# Peripheral-ICs.net
KiCad netlist of a schematic drawn in Altium Designer
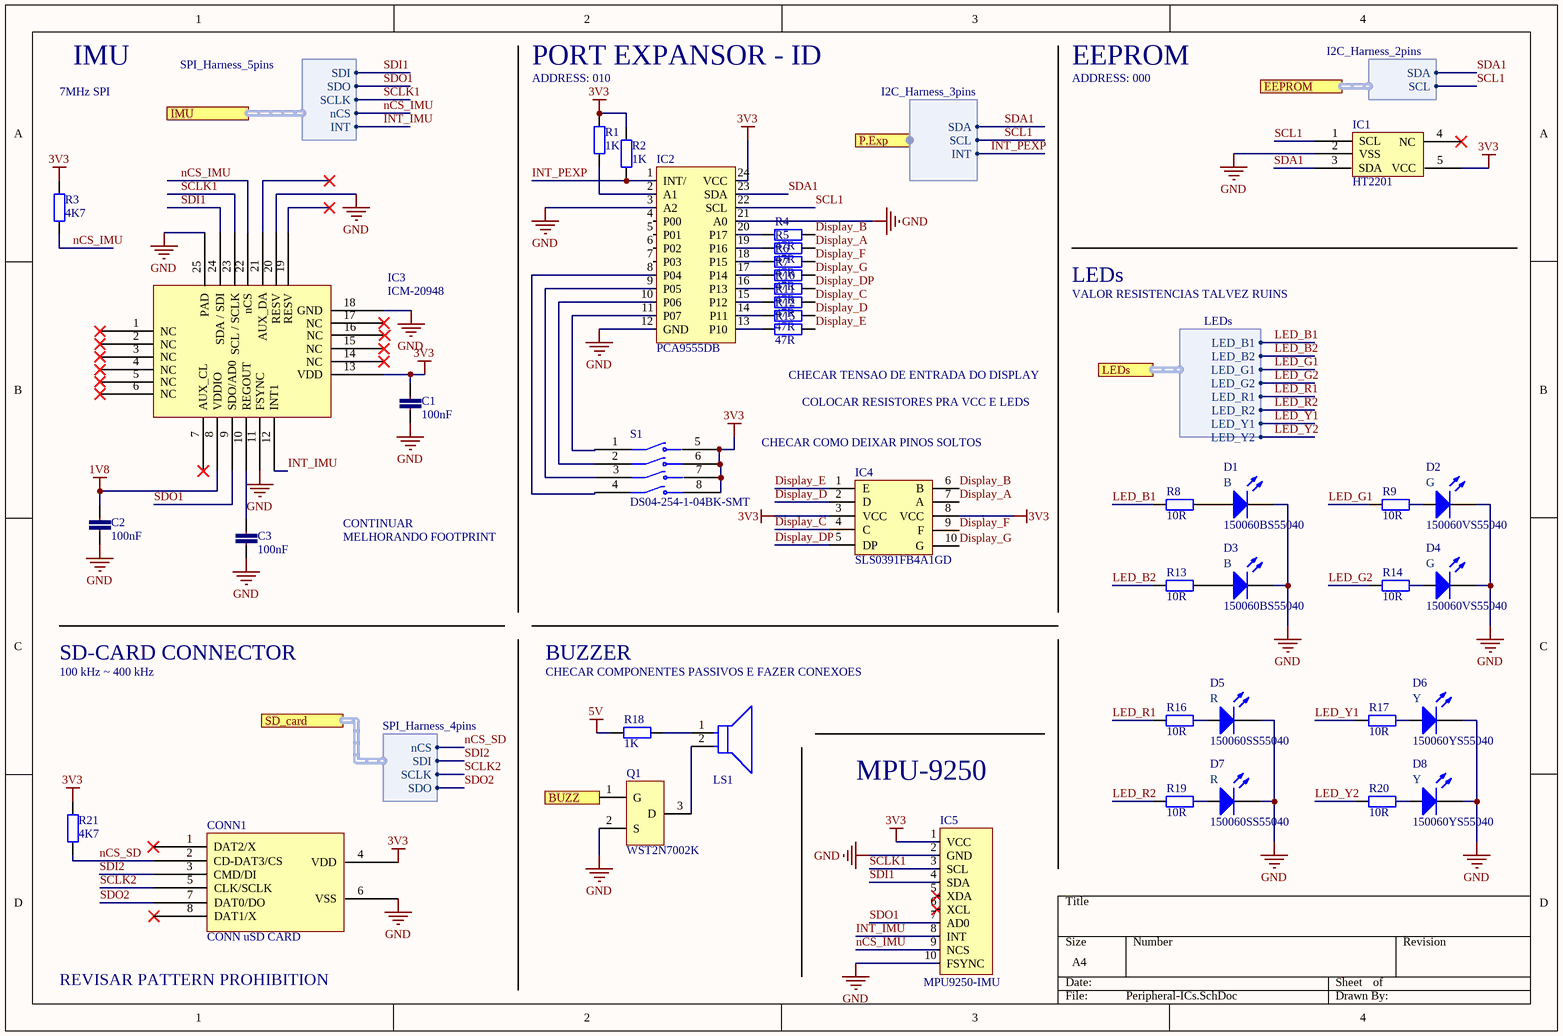
[diagram p0: Peripheral-ICs.SchDoc]

(export (version "E")
  (design (tool "Eeschema 10.0.6"))
  (components
    (comp (ref "C1")
      (value "100nF")
      (footprint "CAP CER 0603")
      (description "Multilayer Ceramic Capacitors MLCC - SMD/SMT 25V 0.1uF 0603 Y5V -20/+80%")
      (fields (field (name "MFR") "KEMET"))
      (libsource (lib "SSL-2020-SchLib1") (part "CAP CER 0603 25V 100nF"))
    )
    (comp (ref "C2")
      (value "100nF")
      (footprint "CAP CER 0603")
      (description "Multilayer Ceramic Capacitors MLCC - SMD/SMT 25V 0.1uF 0603 Y5V -20/+80%")
      (fields (field (name "MFR") "KEMET"))
      (libsource (lib "SSL-2020-SchLib1") (part "CAP CER 0603 25V 100nF"))
    )
    (comp (ref "C3")
      (value "100nF")
      (footprint "CAP CER 0603")
      (description "Multilayer Ceramic Capacitors MLCC - SMD/SMT 25V 0.1uF 0603 Y5V -20/+80%")
      (fields (field (name "MFR") "KEMET"))
      (libsource (lib "SSL-2020-SchLib1") (part "CAP CER 0603 25V 100nF"))
    )
    (comp (ref "CONN1")
      (value "CONN uSD CARD")
      (footprint "2908-05WB-MG")
      (description "8 Position Card Connector Secure Digital - microSD™ Surface Mount, Right Angle Gold")
      (libsource (lib "SSL-2020-SchLib1") (part "2908-05WB-MG"))
    )
    (comp (ref "D1")
      (value "150060BS55040")
      (footprint "LED 0603 BLUE")
      (description "Standard LEDs - SMD WL-SMCD SMD Mono SMD 0603 Blue 465nm")
      (fields (field (name "MFR") "Wurth Elektronik"))
      (libsource (lib "SSL-2020-SchLib1") (part "150060BS55040"))
    )
    (comp (ref "D2")
      (value "150060VS55040")
      (footprint "LED 0603 GREEN")
      (description "Standard LEDs - SMD WL-SMCD SMD MonoChip 0603 BrtGrn 575nm")
      (fields (field (name "MFR") "Wurth Elektronik"))
      (libsource (lib "SSL-2020-SchLib1") (part "150060VS55040"))
    )
    (comp (ref "D3")
      (value "150060BS55040")
      (footprint "LED 0603 BLUE")
      (description "Standard LEDs - SMD WL-SMCD SMD Mono SMD 0603 Blue 465nm")
      (fields (field (name "MFR") "Wurth Elektronik"))
      (libsource (lib "SSL-2020-SchLib1") (part "150060BS55040"))
    )
    (comp (ref "D4")
      (value "150060VS55040")
      (footprint "LED 0603 GREEN")
      (description "Standard LEDs - SMD WL-SMCD SMD MonoChip 0603 BrtGrn 575nm")
      (fields (field (name "MFR") "Wurth Elektronik"))
      (libsource (lib "SSL-2020-SchLib1") (part "150060VS55040"))
    )
    (comp (ref "D5")
      (value "150060SS55040")
      (footprint "LED 0603 RED")
      (description "Standard LEDs - SMD WL-SMCD SMD MonoChip 0603 Super Red 645nm")
      (fields (field (name "MFR") "Wurth Elektronik"))
      (libsource (lib "SSL-2020-SchLib1") (part "150060SS55040"))
    )
    (comp (ref "D6")
      (value "150060YS55040")
      (footprint "LED 0603 YELLOW")
      (description "Standard LEDs - SMD WL-SMCD SMD MonoChip 0603 Yllw 591nm")
      (fields (field (name "MFR") "Wurth Elektronik"))
      (libsource (lib "SSL-2020-SchLib1") (part "150060YS55040"))
    )
    (comp (ref "D7")
      (value "150060SS55040")
      (footprint "LED 0603 RED")
      (description "Standard LEDs - SMD WL-SMCD SMD MonoChip 0603 Super Red 645nm")
      (fields (field (name "MFR") "Wurth Elektronik"))
      (libsource (lib "SSL-2020-SchLib1") (part "150060SS55040"))
    )
    (comp (ref "D8")
      (value "150060YS55040")
      (footprint "LED 0603 YELLOW")
      (description "Standard LEDs - SMD WL-SMCD SMD MonoChip 0603 Yllw 591nm")
      (fields (field (name "MFR") "Wurth Elektronik"))
      (libsource (lib "SSL-2020-SchLib1") (part "150060YS55040"))
    )
    (comp (ref "IC1")
      (value "HT2201")
      (footprint "SOT-23-5")
      (description "EEPROM EEPROM 1KB (128 X 8) I2C SOT-23-5 ROHS")
      (fields (field (name "MFR") "Holtek Semicon"))
      (libsource (lib "SSL-2020-SchLib1") (part "HT2201"))
    )
    (comp (ref "IC2")
      (value "PCA9555DB")
      (footprint "SSOP-24")
      (description "INTERFACE - I/O EXPANDERS SSOP-24 ROHS")
      (fields (field (name "MFR") "NXP Semicon"))
      (libsource (lib "SSL-2020-SchLib1") (part "PCA9555DB"))
    )
    (comp (ref "IC3")
      (value "ICM-20948")
      (footprint "ICM-20948")
      (description "IMU ACCEL/GYRO/COMPI2C/SPI 24QFN")
      (libsource (lib "SSL-2020-SchLib1") (part "ICM-20948"))
    )
    (comp (ref "IC4")
      (value "SLS0391FB4A1GD")
      (footprint "LDS-SMHTA304RISITR")
      (description "1 0.39''(9.91MM) ANODE(POSITIVE ELECTRODE) BLUE 473NM SMD LED SEGMENT DISPLAY ROHS")
      (fields (field (name "MFR") "SUNLIGHT"))
      (libsource (lib "SSL-2020-SchLib1") (part "SLS0391FB4A1GD"))
    )
    (comp (ref "IC5")
      (value "MPU9250-IMU")
      (footprint "MPU9250-IMU")
      (libsource (lib "SSL-2020-SchLib1") (part "MPU9250-IMU"))
    )
    (comp (ref "LS1")
      (value "Speak_TDK_PS1420P02CT_eec")
      (footprint "TDK_PS1420P02CT_0")
      (description "SPEAK AUDIO PIEZO TRANSDUCER 30V TH")
      (fields (field (name "PART NUMBER") "PS1420P02CT") (field (name "MANUFACTURER") "TDK"))
      (libsource (lib "SSL-2020-SchLib1") (part "Speak_TDK_PS1420P02CT_eec"))
    )
    (comp (ref "Q1")
      (value "WST2N7002K")
      (footprint "SOT-23-3")
      (description "MOSFET N TRENCH 60V 300MA 2.5V @ 250UA 3 ? @ 500MA,10V SOT-23(SOT-23-3) ROHS")
      (fields (field (name "MFR") "Winsok Semicon"))
      (libsource (lib "SSL-2020-SchLib1") (part "WST2N7002K"))
    )
    (comp (ref "R1")
      (value "1K")
      (footprint "RES SMD 0603")
      (description "Thick Film Resistors 1/10Watt 1Kohms 1% Commercial Use")
      (fields (field (name "MFR") "Vishay / Dale"))
      (libsource (lib "SSL-2020-SchLib1") (part "RES SMD 0603 1K"))
    )
    (comp (ref "R2")
      (value "1K")
      (footprint "RES SMD 0603")
      (description "Thick Film Resistors 1/10Watt 1Kohms 1% Commercial Use")
      (fields (field (name "MFR") "Vishay / Dale"))
      (libsource (lib "SSL-2020-SchLib1") (part "RES SMD 0603 1K"))
    )
    (comp (ref "R3")
      (value "4K7")
      (footprint "RES SMD 0603")
      (libsource (lib "SSL-2020-SchLib1") (part "RES SMD 0603 4K7"))
    )
    (comp (ref "R4")
      (value "47R")
      (footprint "RES SMD 0603")
      (description "Thick Film Resistors 1/10Watt 47ohms 1% Commercial Use")
      (fields (field (name "MFR") "Vishay / Dale"))
      (libsource (lib "SSL-2020-SchLib1") (part "RES SMD 0603 47R"))
    )
    (comp (ref "R5")
      (value "47R")
      (footprint "RES SMD 0603")
      (description "Thick Film Resistors 1/10Watt 47ohms 1% Commercial Use")
      (fields (field (name "MFR") "Vishay / Dale"))
      (libsource (lib "SSL-2020-SchLib1") (part "RES SMD 0603 47R"))
    )
    (comp (ref "R6")
      (value "47R")
      (footprint "RES SMD 0603")
      (description "Thick Film Resistors 1/10Watt 47ohms 1% Commercial Use")
      (fields (field (name "MFR") "Vishay / Dale"))
      (libsource (lib "SSL-2020-SchLib1") (part "RES SMD 0603 47R"))
    )
    (comp (ref "R7")
      (value "47R")
      (footprint "RES SMD 0603")
      (description "Thick Film Resistors 1/10Watt 47ohms 1% Commercial Use")
      (fields (field (name "MFR") "Vishay / Dale"))
      (libsource (lib "SSL-2020-SchLib1") (part "RES SMD 0603 47R"))
    )
    (comp (ref "R8")
      (value "10R")
      (footprint "RES SMD 0603")
      (description "Thick Film Resistors 1/10Watt 10ohms 1% Commercial Use")
      (fields (field (name "MFR") "Vishay / Dale"))
      (libsource (lib "SSL-2020-SchLib1") (part "RES SMD 0603 10R"))
    )
    (comp (ref "R9")
      (value "10R")
      (footprint "RES SMD 0603")
      (description "Thick Film Resistors 1/10Watt 10ohms 1% Commercial Use")
      (fields (field (name "MFR") "Vishay / Dale"))
      (libsource (lib "SSL-2020-SchLib1") (part "RES SMD 0603 10R"))
    )
    (comp (ref "R10")
      (value "47R")
      (footprint "RES SMD 0603")
      (description "Thick Film Resistors 1/10Watt 47ohms 1% Commercial Use")
      (fields (field (name "MFR") "Vishay / Dale"))
      (libsource (lib "SSL-2020-SchLib1") (part "RES SMD 0603 47R"))
    )
    (comp (ref "R11")
      (value "47R")
      (footprint "RES SMD 0603")
      (description "Thick Film Resistors 1/10Watt 47ohms 1% Commercial Use")
      (fields (field (name "MFR") "Vishay / Dale"))
      (libsource (lib "SSL-2020-SchLib1") (part "RES SMD 0603 47R"))
    )
    (comp (ref "R12")
      (value "47R")
      (footprint "RES SMD 0603")
      (description "Thick Film Resistors 1/10Watt 47ohms 1% Commercial Use")
      (fields (field (name "MFR") "Vishay / Dale"))
      (libsource (lib "SSL-2020-SchLib1") (part "RES SMD 0603 47R"))
    )
    (comp (ref "R13")
      (value "10R")
      (footprint "RES SMD 0603")
      (description "Thick Film Resistors 1/10Watt 10ohms 1% Commercial Use")
      (fields (field (name "MFR") "Vishay / Dale"))
      (libsource (lib "SSL-2020-SchLib1") (part "RES SMD 0603 10R"))
    )
    (comp (ref "R14")
      (value "10R")
      (footprint "RES SMD 0603")
      (description "Thick Film Resistors 1/10Watt 10ohms 1% Commercial Use")
      (fields (field (name "MFR") "Vishay / Dale"))
      (libsource (lib "SSL-2020-SchLib1") (part "RES SMD 0603 10R"))
    )
    (comp (ref "R15")
      (value "47R")
      (footprint "RES SMD 0603")
      (description "Thick Film Resistors 1/10Watt 47ohms 1% Commercial Use")
      (fields (field (name "MFR") "Vishay / Dale"))
      (libsource (lib "SSL-2020-SchLib1") (part "RES SMD 0603 47R"))
    )
    (comp (ref "R16")
      (value "10R")
      (footprint "RES SMD 0603")
      (description "Thick Film Resistors 1/10Watt 10ohms 1% Commercial Use")
      (fields (field (name "MFR") "Vishay / Dale"))
      (libsource (lib "SSL-2020-SchLib1") (part "RES SMD 0603 10R"))
    )
    (comp (ref "R17")
      (value "10R")
      (footprint "RES SMD 0603")
      (description "Thick Film Resistors 1/10Watt 10ohms 1% Commercial Use")
      (fields (field (name "MFR") "Vishay / Dale"))
      (libsource (lib "SSL-2020-SchLib1") (part "RES SMD 0603 10R"))
    )
    (comp (ref "R18")
      (value "1K")
      (footprint "RES SMD 0603")
      (description "Thick Film Resistors 1/10Watt 1Kohms 1% Commercial Use")
      (fields (field (name "MFR") "Vishay / Dale"))
      (libsource (lib "") (part "RES SMD 0603 1K_1"))
    )
    (comp (ref "R19")
      (value "10R")
      (footprint "RES SMD 0603")
      (description "Thick Film Resistors 1/10Watt 10ohms 1% Commercial Use")
      (fields (field (name "MFR") "Vishay / Dale"))
      (libsource (lib "SSL-2020-SchLib1") (part "RES SMD 0603 10R"))
    )
    (comp (ref "R20")
      (value "10R")
      (footprint "RES SMD 0603")
      (description "Thick Film Resistors 1/10Watt 10ohms 1% Commercial Use")
      (fields (field (name "MFR") "Vishay / Dale"))
      (libsource (lib "SSL-2020-SchLib1") (part "RES SMD 0603 10R"))
    )
    (comp (ref "R21")
      (value "4K7")
      (footprint "RES SMD 0603")
      (libsource (lib "SSL-2020-SchLib1") (part "RES SMD 0603 4K7"))
    )
    (comp (ref "S1")
      (value "DS04-254-1-04BK-SMT")
      (footprint "DS04-254-1-04BK-SMT")
      (description "Dip Switch SPST 4 Position Surface Mount Slide (Standard) Actuator 25mA 24VDC")
      (libsource (lib "SSL-2020-SchLib1") (part "DS04-254-1-04BK-SMT"))
    )
  )
  (nets
    (net (code "7") (name "/BUZZ") (class "Default")
      (node (ref "Q1") (pin "1") (pinfunction "G_1") (pintype "passive"))
    )
    (net (code "8") (name "/Display_A") (class "Default")
      (node (ref "IC4") (pin "7") (pinfunction "A_7") (pintype "passive"))
      (node (ref "R5") (pin "2") (pinfunction "2_2") (pintype "passive"))
    )
    (net (code "9") (name "/Display_B") (class "Default")
      (node (ref "IC4") (pin "6") (pinfunction "B_6") (pintype "passive"))
      (node (ref "R4") (pin "2") (pinfunction "2_2") (pintype "passive"))
    )
    (net (code "10") (name "/Display_C") (class "Default")
      (node (ref "IC4") (pin "4") (pinfunction "C_4") (pintype "passive"))
      (node (ref "R11") (pin "2") (pinfunction "2_2") (pintype "passive"))
    )
    (net (code "11") (name "/Display_D") (class "Default")
      (node (ref "IC4") (pin "2") (pinfunction "D_2") (pintype "passive"))
      (node (ref "R12") (pin "2") (pinfunction "2_2") (pintype "passive"))
    )
    (net (code "12") (name "/Display_DP") (class "Default")
      (node (ref "IC4") (pin "5") (pinfunction "DP_5") (pintype "passive"))
      (node (ref "R10") (pin "2") (pinfunction "2_2") (pintype "passive"))
    )
    (net (code "13") (name "/Display_E") (class "Default")
      (node (ref "IC4") (pin "1") (pinfunction "E_1") (pintype "passive"))
      (node (ref "R15") (pin "2") (pinfunction "2_2") (pintype "passive"))
    )
    (net (code "14") (name "/Display_F") (class "Default")
      (node (ref "IC4") (pin "9") (pinfunction "F_9") (pintype "passive"))
      (node (ref "R6") (pin "2") (pinfunction "2_2") (pintype "passive"))
    )
    (net (code "15") (name "/Display_G") (class "Default")
      (node (ref "IC4") (pin "10") (pinfunction "G_10") (pintype "passive"))
      (node (ref "R7") (pin "2") (pinfunction "2_2") (pintype "passive"))
    )
    (net (code "16") (name "/INT_IMU") (class "Default")
      (node (ref "IC3") (pin "12") (pinfunction "INT1_12") (pintype "passive"))
      (node (ref "IC5") (pin "8") (pinfunction "INT_8") (pintype "passive"))
    )
    (net (code "17") (name "/INT_PEXP") (class "Default")
      (node (ref "IC2") (pin "1") (pinfunction "INT/_1") (pintype "passive"))
      (node (ref "R2") (pin "1") (pinfunction "1_1") (pintype "passive"))
    )
    (net (code "18") (name "/LED_B1") (class "Default")
      (node (ref "R8") (pin "2") (pinfunction "2_2") (pintype "passive"))
    )
    (net (code "19") (name "/LED_B2") (class "Default")
      (node (ref "R13") (pin "2") (pinfunction "2_2") (pintype "passive"))
    )
    (net (code "20") (name "/LED_G1") (class "Default")
      (node (ref "R9") (pin "2") (pinfunction "2_2") (pintype "passive"))
    )
    (net (code "21") (name "/LED_G2") (class "Default")
      (node (ref "R14") (pin "2") (pinfunction "2_2") (pintype "passive"))
    )
    (net (code "22") (name "/LED_R1") (class "Default")
      (node (ref "R16") (pin "2") (pinfunction "2_2") (pintype "passive"))
    )
    (net (code "23") (name "/LED_R2") (class "Default")
      (node (ref "R19") (pin "2") (pinfunction "2_2") (pintype "passive"))
    )
    (net (code "24") (name "/LED_Y1") (class "Default")
      (node (ref "R17") (pin "2") (pinfunction "2_2") (pintype "passive"))
    )
    (net (code "25") (name "/LED_Y2") (class "Default")
      (node (ref "R20") (pin "2") (pinfunction "2_2") (pintype "passive"))
    )
    (net (code "26") (name "/SCL1") (class "Default")
      (node (ref "IC1") (pin "1") (pinfunction "SCL_1") (pintype "passive"))
      (node (ref "IC2") (pin "22") (pinfunction "SCL_22") (pintype "passive"))
    )
    (net (code "27") (name "/SCLK1") (class "Default")
      (node (ref "IC3") (pin "23") (pinfunction "SCL_/_SCLK_23") (pintype "passive"))
      (node (ref "IC5") (pin "3") (pinfunction "SCL_3") (pintype "passive"))
    )
    (net (code "28") (name "/SCLK2") (class "Default")
      (node (ref "CONN1") (pin "5") (pinfunction "CLK/SCLK_5") (pintype "passive"))
    )
    (net (code "29") (name "/SDA1") (class "Default")
      (node (ref "IC1") (pin "3") (pinfunction "SDA_3") (pintype "passive"))
      (node (ref "IC2") (pin "23") (pinfunction "SDA_23") (pintype "passive"))
    )
    (net (code "30") (name "/SDI1") (class "Default")
      (node (ref "IC3") (pin "24") (pinfunction "SDA_/_SDI_24") (pintype "passive"))
      (node (ref "IC5") (pin "4") (pinfunction "SDA_4") (pintype "passive"))
    )
    (net (code "31") (name "/SDI2") (class "Default")
      (node (ref "CONN1") (pin "3") (pinfunction "CMD/DI_3") (pintype "passive"))
    )
    (net (code "32") (name "/SDO1") (class "Default")
      (node (ref "IC3") (pin "9") (pinfunction "SDO/AD0_9") (pintype "passive"))
      (node (ref "IC5") (pin "7") (pinfunction "AD0_7") (pintype "passive"))
    )
    (net (code "33") (name "/SDO2") (class "Default")
      (node (ref "CONN1") (pin "7") (pinfunction "DAT0/DO_7") (pintype "power_in"))
    )
    (net (code "34") (name "/nCS_IMU") (class "Default")
      (node (ref "IC3") (pin "22") (pinfunction "nCS_22") (pintype "passive"))
      (node (ref "IC5") (pin "9") (pinfunction "NCS_9") (pintype "passive"))
      (node (ref "R3") (pin "1") (pinfunction "1_1") (pintype "passive"))
    )
    (net (code "35") (name "/nCS_SD") (class "Default")
      (node (ref "CONN1") (pin "2") (pinfunction "CD-DAT3/CS_2") (pintype "passive"))
      (node (ref "R21") (pin "1") (pinfunction "1_1") (pintype "passive"))
    )
    (net (code "41") (name "1V8") (class "Default")
      (node (ref "C2") (pin "1") (pinfunction "1_1") (pintype "passive"))
      (node (ref "IC3") (pin "8") (pinfunction "VDDIO_8") (pintype "passive"))
    )
    (net (code "42") (name "3V3") (class "Default")
      (node (ref "C1") (pin "1") (pinfunction "1_1") (pintype "passive"))
      (node (ref "CONN1") (pin "4") (pinfunction "VDD_4") (pintype "passive"))
      (node (ref "IC1") (pin "5") (pinfunction "VCC_5") (pintype "passive"))
      (node (ref "IC2") (pin "24") (pinfunction "VCC_24") (pintype "passive"))
      (node (ref "IC3") (pin "13") (pinfunction "VDD_13") (pintype "passive"))
      (node (ref "IC4") (pin "3") (pinfunction "VCC_3") (pintype "passive"))
      (node (ref "IC4") (pin "8") (pinfunction "VCC_8") (pintype "passive"))
      (node (ref "IC5") (pin "1") (pinfunction "VCC_1") (pintype "passive"))
      (node (ref "R1") (pin "2") (pinfunction "2_2") (pintype "passive"))
      (node (ref "R2") (pin "2") (pinfunction "2_2") (pintype "passive"))
      (node (ref "R21") (pin "2") (pinfunction "2_2") (pintype "passive"))
      (node (ref "R3") (pin "2") (pinfunction "2_2") (pintype "passive"))
      (node (ref "S1") (pin "5") (pinfunction "5_5") (pintype "passive"))
      (node (ref "S1") (pin "6") (pinfunction "6_6") (pintype "passive"))
      (node (ref "S1") (pin "7") (pinfunction "7_7") (pintype "passive"))
      (node (ref "S1") (pin "8") (pinfunction "8_8") (pintype "passive"))
    )
    (net (code "43") (name "5V") (class "Default")
      (node (ref "R18") (pin "2") (pinfunction "2_2") (pintype "passive"))
    )
    (net (code "44") (name "GND") (class "Default")
      (node (ref "C1") (pin "2") (pinfunction "2_2") (pintype "passive"))
      (node (ref "C2") (pin "2") (pinfunction "2_2") (pintype "passive"))
      (node (ref "C3") (pin "2") (pinfunction "2_2") (pintype "passive"))
      (node (ref "CONN1") (pin "6") (pinfunction "VSS_6") (pintype "passive"))
      (node (ref "D1") (pin "2") (pinfunction "N_2") (pintype "passive"))
      (node (ref "D2") (pin "2") (pinfunction "N_2") (pintype "passive"))
      (node (ref "D3") (pin "2") (pinfunction "N_2") (pintype "passive"))
      (node (ref "D4") (pin "2") (pinfunction "N_2") (pintype "passive"))
      (node (ref "D5") (pin "2") (pinfunction "N_2") (pintype "passive"))
      (node (ref "D6") (pin "2") (pinfunction "N_2") (pintype "passive"))
      (node (ref "D7") (pin "2") (pinfunction "N_2") (pintype "passive"))
      (node (ref "D8") (pin "2") (pinfunction "N_2") (pintype "passive"))
      (node (ref "IC1") (pin "2") (pinfunction "VSS_2") (pintype "passive"))
      (node (ref "IC2") (pin "12") (pinfunction "GND_12") (pintype "passive"))
      (node (ref "IC2") (pin "21") (pinfunction "A0_21") (pintype "passive"))
      (node (ref "IC2") (pin "3") (pinfunction "A2_3") (pintype "passive"))
      (node (ref "IC3") (pin "11") (pinfunction "FSYNC_11") (pintype "passive"))
      (node (ref "IC3") (pin "18") (pinfunction "GND_18") (pintype "passive"))
      (node (ref "IC3") (pin "20") (pinfunction "RESV_20") (pintype "passive"))
      (node (ref "IC3") (pin "25") (pinfunction "PAD_25") (pintype "passive"))
      (node (ref "IC5") (pin "10") (pinfunction "FSYNC_10") (pintype "passive"))
      (node (ref "IC5") (pin "2") (pinfunction "GND_2") (pintype "passive"))
      (node (ref "Q1") (pin "2") (pinfunction "S_2") (pintype "passive"))
    )
    (net (code "45") (name "Net-(D1-P)") (class "Default")
      (node (ref "D1") (pin "1") (pinfunction "P_1") (pintype "passive"))
      (node (ref "R8") (pin "1") (pinfunction "1_1") (pintype "passive"))
    )
    (net (code "46") (name "Net-(D2-P)") (class "Default")
      (node (ref "D2") (pin "1") (pinfunction "P_1") (pintype "passive"))
      (node (ref "R9") (pin "1") (pinfunction "1_1") (pintype "passive"))
    )
    (net (code "47") (name "Net-(D3-P)") (class "Default")
      (node (ref "D3") (pin "1") (pinfunction "P_1") (pintype "passive"))
      (node (ref "R13") (pin "1") (pinfunction "1_1") (pintype "passive"))
    )
    (net (code "48") (name "Net-(D4-P)") (class "Default")
      (node (ref "D4") (pin "1") (pinfunction "P_1") (pintype "passive"))
      (node (ref "R14") (pin "1") (pinfunction "1_1") (pintype "passive"))
    )
    (net (code "49") (name "Net-(D5-P)") (class "Default")
      (node (ref "D5") (pin "1") (pinfunction "P_1") (pintype "passive"))
      (node (ref "R16") (pin "1") (pinfunction "1_1") (pintype "passive"))
    )
    (net (code "50") (name "Net-(D6-P)") (class "Default")
      (node (ref "D6") (pin "1") (pinfunction "P_1") (pintype "passive"))
      (node (ref "R17") (pin "1") (pinfunction "1_1") (pintype "passive"))
    )
    (net (code "51") (name "Net-(D7-P)") (class "Default")
      (node (ref "D7") (pin "1") (pinfunction "P_1") (pintype "passive"))
      (node (ref "R19") (pin "1") (pinfunction "1_1") (pintype "passive"))
    )
    (net (code "52") (name "Net-(D8-P)") (class "Default")
      (node (ref "D8") (pin "1") (pinfunction "P_1") (pintype "passive"))
      (node (ref "R20") (pin "1") (pinfunction "1_1") (pintype "passive"))
    )
    (net (code "53") (name "Net-(IC2-A1)") (class "Default")
      (node (ref "IC2") (pin "2") (pinfunction "A1_2") (pintype "passive"))
      (node (ref "R1") (pin "1") (pinfunction "1_1") (pintype "passive"))
    )
    (net (code "54") (name "Net-(IC2-P04)") (class "Default")
      (node (ref "IC2") (pin "8") (pinfunction "P04_8") (pintype "passive"))
      (node (ref "S1") (pin "4") (pinfunction "4_4") (pintype "passive"))
    )
    (net (code "55") (name "Net-(IC2-P05)") (class "Default")
      (node (ref "IC2") (pin "9") (pinfunction "P05_9") (pintype "passive"))
      (node (ref "S1") (pin "3") (pinfunction "3_3") (pintype "passive"))
    )
    (net (code "56") (name "Net-(IC2-P06)") (class "Default")
      (node (ref "IC2") (pin "10") (pinfunction "P06_10") (pintype "passive"))
      (node (ref "S1") (pin "2") (pinfunction "2_2") (pintype "passive"))
    )
    (net (code "57") (name "Net-(IC2-P07)") (class "Default")
      (node (ref "IC2") (pin "11") (pinfunction "P07_11") (pintype "passive"))
      (node (ref "S1") (pin "1") (pinfunction "1_1") (pintype "passive"))
    )
    (net (code "58") (name "Net-(IC2-P10)") (class "Default")
      (node (ref "IC2") (pin "13") (pinfunction "P10_13") (pintype "passive"))
      (node (ref "R15") (pin "1") (pinfunction "1_1") (pintype "passive"))
    )
    (net (code "59") (name "Net-(IC2-P11)") (class "Default")
      (node (ref "IC2") (pin "14") (pinfunction "P11_14") (pintype "passive"))
      (node (ref "R12") (pin "1") (pinfunction "1_1") (pintype "passive"))
    )
    (net (code "60") (name "Net-(IC2-P12)") (class "Default")
      (node (ref "IC2") (pin "15") (pinfunction "P12_15") (pintype "passive"))
      (node (ref "R11") (pin "1") (pinfunction "1_1") (pintype "passive"))
    )
    (net (code "61") (name "Net-(IC2-P13)") (class "Default")
      (node (ref "IC2") (pin "16") (pinfunction "P13_16") (pintype "passive"))
      (node (ref "R10") (pin "1") (pinfunction "1_1") (pintype "passive"))
    )
    (net (code "62") (name "Net-(IC2-P14)") (class "Default")
      (node (ref "IC2") (pin "17") (pinfunction "P14_17") (pintype "passive"))
      (node (ref "R7") (pin "1") (pinfunction "1_1") (pintype "passive"))
    )
    (net (code "63") (name "Net-(IC2-P15)") (class "Default")
      (node (ref "IC2") (pin "18") (pinfunction "P15_18") (pintype "passive"))
      (node (ref "R6") (pin "1") (pinfunction "1_1") (pintype "passive"))
    )
    (net (code "64") (name "Net-(IC2-P16)") (class "Default")
      (node (ref "IC2") (pin "19") (pinfunction "P16_19") (pintype "passive"))
      (node (ref "R5") (pin "1") (pinfunction "1_1") (pintype "passive"))
    )
    (net (code "65") (name "Net-(IC2-P17)") (class "Default")
      (node (ref "IC2") (pin "20") (pinfunction "P17_20") (pintype "passive"))
      (node (ref "R4") (pin "1") (pinfunction "1_1") (pintype "passive"))
    )
    (net (code "66") (name "Net-(IC3-REGOUT)") (class "Default")
      (node (ref "C3") (pin "1") (pinfunction "1_1") (pintype "passive"))
      (node (ref "IC3") (pin "10") (pinfunction "REGOUT_10") (pintype "passive"))
    )
    (net (code "67") (name "Net-(LS1-Pad1)") (class "Default")
      (node (ref "LS1") (pin "1") (pinfunction "1_1") (pintype "passive"))
      (node (ref "R18") (pin "1") (pinfunction "1_1") (pintype "passive"))
    )
    (net (code "68") (name "Net-(Q1-D)") (class "Default")
      (node (ref "LS1") (pin "2") (pinfunction "2_2") (pintype "passive"))
      (node (ref "Q1") (pin "3") (pinfunction "D_3") (pintype "passive"))
    )
    (net (code "69") (name "unconnected-(CONN1-DAT1{slash}X-Pad8)") (class "Default")
      (node (ref "CONN1") (pin "8") (pinfunction "DAT1/X_8") (pintype "power_in+no_connect"))
    )
    (net (code "70") (name "unconnected-(CONN1-DAT2{slash}X-Pad1)") (class "Default")
      (node (ref "CONN1") (pin "1") (pinfunction "DAT2/X_1") (pintype "passive+no_connect"))
    )
    (net (code "71") (name "unconnected-(IC1-NC-Pad4)") (class "Default")
      (node (ref "IC1") (pin "4") (pinfunction "NC_4") (pintype "passive+no_connect"))
    )
    (net (code "72") (name "unconnected-(IC2-P00-Pad4)") (class "Default")
      (node (ref "IC2") (pin "4") (pinfunction "P00_4") (pintype "passive"))
    )
    (net (code "73") (name "unconnected-(IC2-P01-Pad5)") (class "Default")
      (node (ref "IC2") (pin "5") (pinfunction "P01_5") (pintype "passive"))
    )
    (net (code "74") (name "unconnected-(IC2-P02-Pad6)") (class "Default")
      (node (ref "IC2") (pin "6") (pinfunction "P02_6") (pintype "passive"))
    )
    (net (code "75") (name "unconnected-(IC2-P03-Pad7)") (class "Default")
      (node (ref "IC2") (pin "7") (pinfunction "P03_7") (pintype "passive"))
    )
    (net (code "76") (name "unconnected-(IC3-AUX_CL-Pad7)") (class "Default")
      (node (ref "IC3") (pin "7") (pinfunction "AUX_CL_7") (pintype "passive+no_connect"))
    )
    (net (code "77") (name "unconnected-(IC3-AUX_DA-Pad21)") (class "Default")
      (node (ref "IC3") (pin "21") (pinfunction "AUX_DA_21") (pintype "passive+no_connect"))
    )
    (net (code "78") (name "unconnected-(IC3-NC-Pad1)") (class "Default")
      (node (ref "IC3") (pin "1") (pinfunction "NC_1") (pintype "passive+no_connect"))
    )
    (net (code "79") (name "unconnected-(IC3-NC-Pad2)") (class "Default")
      (node (ref "IC3") (pin "2") (pinfunction "NC_2") (pintype "passive+no_connect"))
    )
    (net (code "80") (name "unconnected-(IC3-NC-Pad3)") (class "Default")
      (node (ref "IC3") (pin "3") (pinfunction "NC_3") (pintype "passive+no_connect"))
    )
    (net (code "81") (name "unconnected-(IC3-NC-Pad4)") (class "Default")
      (node (ref "IC3") (pin "4") (pinfunction "NC_4") (pintype "passive+no_connect"))
    )
    (net (code "82") (name "unconnected-(IC3-NC-Pad5)") (class "Default")
      (node (ref "IC3") (pin "5") (pinfunction "NC_5") (pintype "passive+no_connect"))
    )
    (net (code "83") (name "unconnected-(IC3-NC-Pad6)") (class "Default")
      (node (ref "IC3") (pin "6") (pinfunction "NC_6") (pintype "passive+no_connect"))
    )
    (net (code "84") (name "unconnected-(IC3-NC-Pad14)") (class "Default")
      (node (ref "IC3") (pin "14") (pinfunction "NC_14") (pintype "passive+no_connect"))
    )
    (net (code "85") (name "unconnected-(IC3-NC-Pad15)") (class "Default")
      (node (ref "IC3") (pin "15") (pinfunction "NC_15") (pintype "passive+no_connect"))
    )
    (net (code "86") (name "unconnected-(IC3-NC-Pad16)") (class "Default")
      (node (ref "IC3") (pin "16") (pinfunction "NC_16") (pintype "passive+no_connect"))
    )
    (net (code "87") (name "unconnected-(IC3-NC-Pad17)") (class "Default")
      (node (ref "IC3") (pin "17") (pinfunction "NC_17") (pintype "passive+no_connect"))
    )
    (net (code "88") (name "unconnected-(IC3-RESV-Pad19)") (class "Default")
      (node (ref "IC3") (pin "19") (pinfunction "RESV_19") (pintype "passive+no_connect"))
    )
    (net (code "89") (name "unconnected-(IC5-XCL-Pad6)") (class "Default")
      (node (ref "IC5") (pin "6") (pinfunction "XCL_6") (pintype "passive+no_connect"))
    )
    (net (code "90") (name "unconnected-(IC5-XDA-Pad5)") (class "Default")
      (node (ref "IC5") (pin "5") (pinfunction "XDA_5") (pintype "passive+no_connect"))
    )
  )
)
